# Beambreak_Array_L_-_Emmiter.net
KiCad netlist of a schematic drawn in Altium Designer
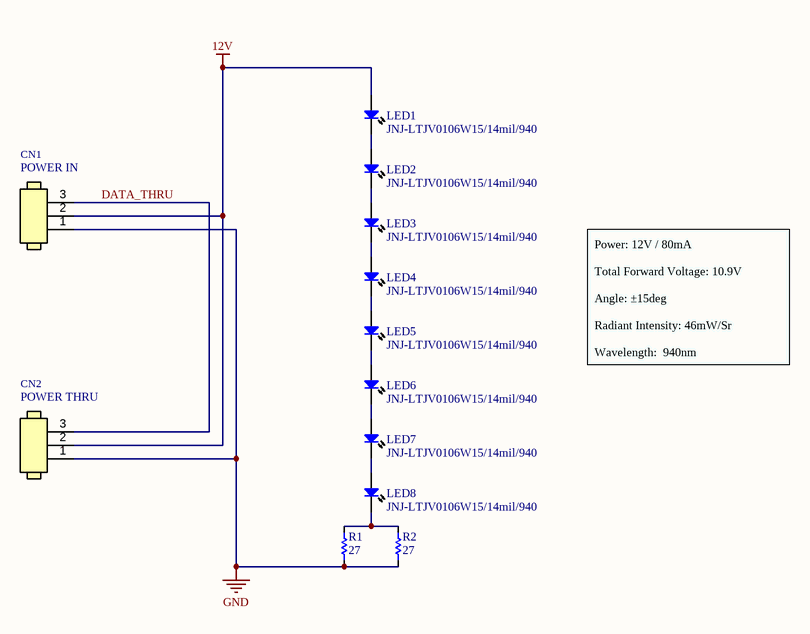
[diagram p0: Beambreak Array L - Emmiter.SchDoc]

(export (version "E")
  (design (tool "Eeschema 10.0.6"))
  (components
    (comp (ref "CN1")
      (value "POWER IN")
      (footprint "EH_1X3P")
      (description "Connector Header, EH Series, 3 Position, 2.5mm, Through Hole, Press-Fit, Solder, Natural")
      (fields (field (name "PARTNUMBER") "B3B-EH-A(LF)(SN)"))
      (libsource (lib "Sainsbury Wellcome Centre") (part "Wire to Board 1x3"))
    )
    (comp (ref "CN2")
      (value "POWER THRU")
      (footprint "EH_1X3P")
      (description "Connector Header, EH Series, 3 Position, 2.5mm, Through Hole, Press-Fit, Solder, Natural")
      (fields (field (name "PARTNUMBER") "B3B-EH-A(LF)(SN)"))
      (libsource (lib "Sainsbury Wellcome Centre") (part "Wire to Board 1x3"))
    )
    (comp (ref "LED1")
      (value "LED2835_IR_940nm")
      (footprint "LED_CHIP_3528 - lens - S")
      (description "240mW/sr 5V 100mA 1.4V~2.1V 925nm~955nm SMD2835-2P LED")
      (fields (field (name "PARTNUMBER") "JNJ-LTJV0106W15/14mil/940"))
      (libsource (lib "Sainsbury Wellcome Centre") (part "LED-IR"))
    )
    (comp (ref "LED2")
      (value "LED2835_IR_940nm")
      (footprint "LED_CHIP_3528 - lens - S")
      (description "240mW/sr 5V 100mA 1.4V~2.1V 925nm~955nm SMD2835-2P LED")
      (fields (field (name "PARTNUMBER") "JNJ-LTJV0106W15/14mil/940"))
      (libsource (lib "Sainsbury Wellcome Centre") (part "LED-IR"))
    )
    (comp (ref "LED3")
      (value "LED2835_IR_940nm")
      (footprint "LED_CHIP_3528 - lens - S")
      (description "240mW/sr 5V 100mA 1.4V~2.1V 925nm~955nm SMD2835-2P LED")
      (fields (field (name "PARTNUMBER") "JNJ-LTJV0106W15/14mil/940"))
      (libsource (lib "Sainsbury Wellcome Centre") (part "LED-IR"))
    )
    (comp (ref "LED4")
      (value "LED2835_IR_940nm")
      (footprint "LED_CHIP_3528 - lens - S")
      (description "240mW/sr 5V 100mA 1.4V~2.1V 925nm~955nm SMD2835-2P LED")
      (fields (field (name "PARTNUMBER") "JNJ-LTJV0106W15/14mil/940"))
      (libsource (lib "Sainsbury Wellcome Centre") (part "LED-IR"))
    )
    (comp (ref "LED5")
      (value "LED2835_IR_940nm")
      (footprint "LED_CHIP_3528 - lens - S")
      (description "240mW/sr 5V 100mA 1.4V~2.1V 925nm~955nm SMD2835-2P LED")
      (fields (field (name "PARTNUMBER") "JNJ-LTJV0106W15/14mil/940"))
      (libsource (lib "Sainsbury Wellcome Centre") (part "LED-IR"))
    )
    (comp (ref "LED6")
      (value "LED2835_IR_940nm")
      (footprint "LED_CHIP_3528 - lens - S")
      (description "240mW/sr 5V 100mA 1.4V~2.1V 925nm~955nm SMD2835-2P LED")
      (fields (field (name "PARTNUMBER") "JNJ-LTJV0106W15/14mil/940"))
      (libsource (lib "Sainsbury Wellcome Centre") (part "LED-IR"))
    )
    (comp (ref "LED7")
      (value "LED2835_IR_940nm")
      (footprint "LED_CHIP_3528 - lens - S")
      (description "240mW/sr 5V 100mA 1.4V~2.1V 925nm~955nm SMD2835-2P LED")
      (fields (field (name "PARTNUMBER") "JNJ-LTJV0106W15/14mil/940"))
      (libsource (lib "Sainsbury Wellcome Centre") (part "LED-IR"))
    )
    (comp (ref "LED8")
      (value "LED2835_IR_940nm")
      (footprint "LED_CHIP_3528 - lens - S")
      (description "240mW/sr 5V 100mA 1.4V~2.1V 925nm~955nm SMD2835-2P LED")
      (fields (field (name "PARTNUMBER") "JNJ-LTJV0106W15/14mil/940"))
      (libsource (lib "Sainsbury Wellcome Centre") (part "LED-IR"))
    )
    (comp (ref "R1")
      (value "27")
      (footprint "RES_CHIP_0805")
      (description "125mW Thick Film Resistors 150V ±100ppm/℃ ±1% 0805 Chip Resistor")
      (fields (field (name "TOLERANCE") "1%") (field (name "PARTNUMBER") "0805W8F270JT5E"))
      (libsource (lib "Sainsbury Wellcome Centre") (part "Res"))
    )
    (comp (ref "R2")
      (value "27")
      (footprint "RES_CHIP_0805")
      (description "125mW Thick Film Resistors 150V ±100ppm/℃ ±1% 0805 Chip Resistor")
      (fields (field (name "TOLERANCE") "1%") (field (name "PARTNUMBER") "0805W8F270JT5E"))
      (libsource (lib "Sainsbury Wellcome Centre") (part "Res"))
    )
  )
  (nets
    (net (code "1") (name "/DATA_THRU") (class "Default")
      (node (ref "CN1") (pin "3") (pinfunction "3_3") (pintype "passive"))
      (node (ref "CN2") (pin "3") (pinfunction "3_3") (pintype "passive"))
    )
    (net (code "2") (name "12V") (class "Default")
      (node (ref "CN1") (pin "2") (pinfunction "2_2") (pintype "passive"))
      (node (ref "CN2") (pin "2") (pinfunction "2_2") (pintype "passive"))
      (node (ref "LED1") (pin "2") (pinfunction "A_2") (pintype "passive"))
    )
    (net (code "3") (name "GND") (class "Default")
      (node (ref "CN1") (pin "1") (pinfunction "1_1") (pintype "passive"))
      (node (ref "CN2") (pin "1") (pinfunction "1_1") (pintype "passive"))
      (node (ref "R1") (pin "1") (pinfunction "1_1") (pintype "passive"))
      (node (ref "R2") (pin "1") (pinfunction "1_1") (pintype "passive"))
    )
    (net (code "4") (name "Net-(LED1-C)") (class "Default")
      (node (ref "LED1") (pin "1") (pinfunction "C_1") (pintype "passive"))
      (node (ref "LED2") (pin "2") (pinfunction "A_2") (pintype "passive"))
    )
    (net (code "5") (name "Net-(LED2-C)") (class "Default")
      (node (ref "LED2") (pin "1") (pinfunction "C_1") (pintype "passive"))
      (node (ref "LED3") (pin "2") (pinfunction "A_2") (pintype "passive"))
    )
    (net (code "6") (name "Net-(LED3-C)") (class "Default")
      (node (ref "LED3") (pin "1") (pinfunction "C_1") (pintype "passive"))
      (node (ref "LED4") (pin "2") (pinfunction "A_2") (pintype "passive"))
    )
    (net (code "7") (name "Net-(LED4-C)") (class "Default")
      (node (ref "LED4") (pin "1") (pinfunction "C_1") (pintype "passive"))
      (node (ref "LED5") (pin "2") (pinfunction "A_2") (pintype "passive"))
    )
    (net (code "8") (name "Net-(LED5-C)") (class "Default")
      (node (ref "LED5") (pin "1") (pinfunction "C_1") (pintype "passive"))
      (node (ref "LED6") (pin "2") (pinfunction "A_2") (pintype "passive"))
    )
    (net (code "9") (name "Net-(LED6-C)") (class "Default")
      (node (ref "LED6") (pin "1") (pinfunction "C_1") (pintype "passive"))
      (node (ref "LED7") (pin "2") (pinfunction "A_2") (pintype "passive"))
    )
    (net (code "10") (name "Net-(LED7-C)") (class "Default")
      (node (ref "LED7") (pin "1") (pinfunction "C_1") (pintype "passive"))
      (node (ref "LED8") (pin "2") (pinfunction "A_2") (pintype "passive"))
    )
    (net (code "11") (name "Net-(LED8-C)") (class "Default")
      (node (ref "LED8") (pin "1") (pinfunction "C_1") (pintype "passive"))
      (node (ref "R1") (pin "2") (pinfunction "2_2") (pintype "passive"))
      (node (ref "R2") (pin "2") (pinfunction "2_2") (pintype "passive"))
    )
  )
)
